# MotherBoard_ver1.net
KiCad netlist of a schematic drawn in EAGLE
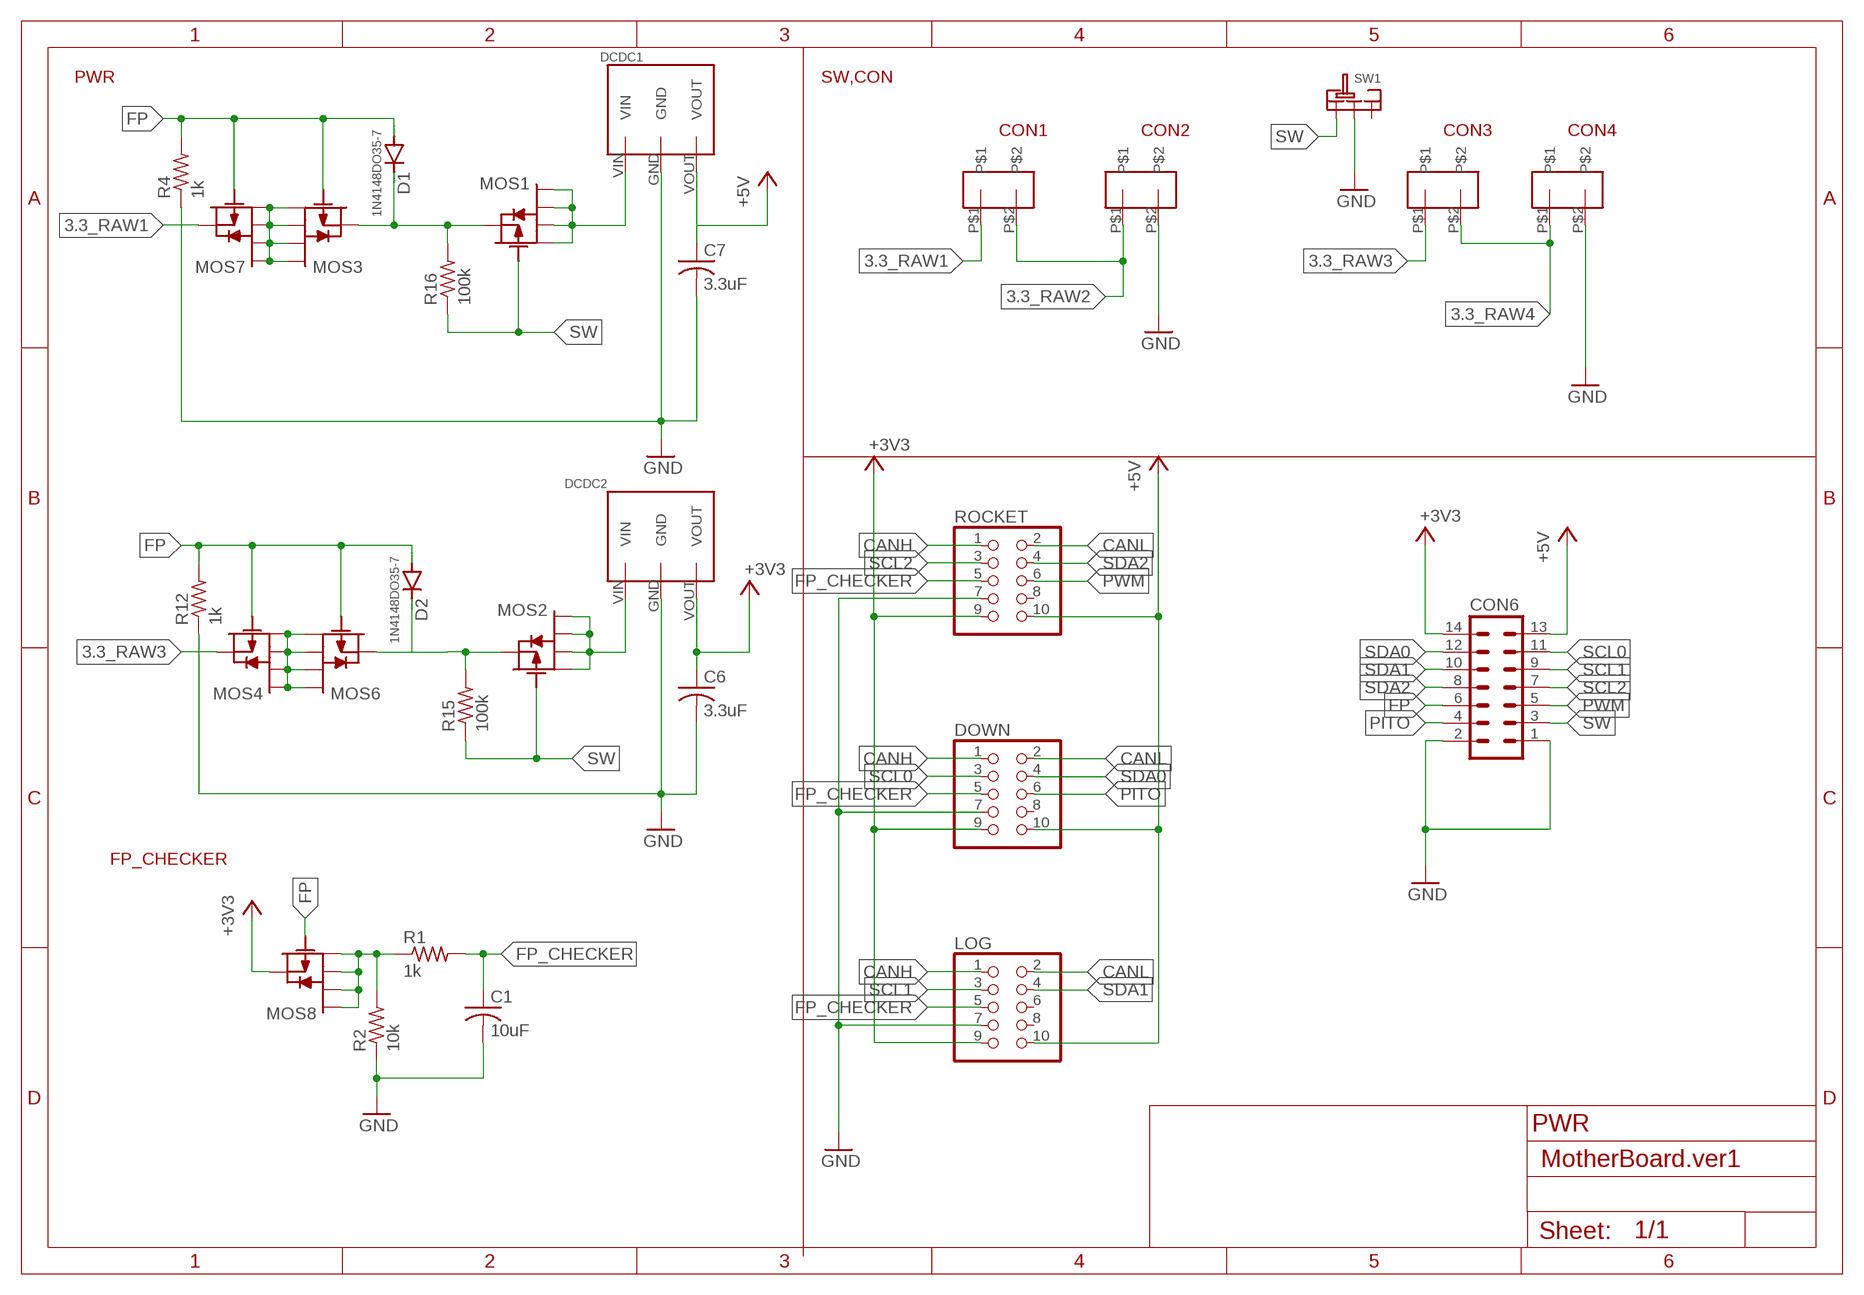
[diagram p0: schematic, sheet 1]

(export (version "E")
  (design (tool "Eeschema 10.0.6"))
  (components
    (comp (ref "C1")
      (value "10uF")
      (footprint "eagle-import:C0603")
      (libsource (lib "eagle-import") (part "C-USC0603"))
    )
    (comp (ref "C6")
      (value "3.3uF")
      (footprint "eagle-import:C0603")
      (libsource (lib "eagle-import") (part "C-USC0603"))
    )
    (comp (ref "C7")
      (value "3.3uF")
      (footprint "eagle-import:C0603")
      (libsource (lib "eagle-import") (part "C-USC0603"))
    )
    (comp (ref "CON1")
      (value "1.25CON2PIN")
      (footprint "eagle-import:1.25CON2PIN")
      (libsource (lib "eagle-import") (part "1.25CON2PIN"))
    )
    (comp (ref "CON2")
      (value "1.25CON2PIN")
      (footprint "eagle-import:1.25CON2PIN")
      (libsource (lib "eagle-import") (part "1.25CON2PIN"))
    )
    (comp (ref "CON3")
      (value "1.25CON2PIN")
      (footprint "eagle-import:1.25CON2PIN")
      (libsource (lib "eagle-import") (part "1.25CON2PIN"))
    )
    (comp (ref "CON4")
      (value "1.25CON2PIN")
      (footprint "eagle-import:1.25CON2PIN")
      (libsource (lib "eagle-import") (part "1.25CON2PIN"))
    )
    (comp (ref "CON6")
      (value "ML14L")
      (footprint "eagle-import:ML14L")
      (libsource (lib "eagle-import") (part "ML14L"))
    )
    (comp (ref "D1")
      (value "1N4148DO35-7")
      (footprint "eagle-import:DO35-7")
      (libsource (lib "eagle-import") (part "1N4148DO35-7"))
    )
    (comp (ref "D2")
      (value "1N4148DO35-7")
      (footprint "eagle-import:DO35-7")
      (libsource (lib "eagle-import") (part "1N4148DO35-7"))
    )
    (comp (ref "DCDC1")
      (value "5V1A_M78AR05-1")
      (footprint "eagle-import:5V1A_M78AR05-1")
      (libsource (lib "eagle-import") (part "5V1A_M78AR05-1"))
    )
    (comp (ref "DCDC2")
      (value "3.3V1A_M78AR033-1")
      (footprint "eagle-import:3.3V1A_M78AR033-1")
      (libsource (lib "eagle-import") (part "3.3V1A_M78AR033-1"))
    )
    (comp (ref "DOWN")
      (value "PINHD-2X5")
      (footprint "eagle-import:2X05")
      (libsource (lib "eagle-import") (part "PINHD-2X5"))
    )
    (comp (ref "LOG")
      (value "PINHD-2X5")
      (footprint "eagle-import:2X05")
      (libsource (lib "eagle-import") (part "PINHD-2X5"))
    )
    (comp (ref "MOS1")
      (value "PCH_SSM6J808R")
      (footprint "eagle-import:SSM6J808R")
      (libsource (lib "eagle-import") (part "PCH_SSM6J808R"))
    )
    (comp (ref "MOS2")
      (value "PCH_SSM6J808R")
      (footprint "eagle-import:SSM6J808R")
      (libsource (lib "eagle-import") (part "PCH_SSM6J808R"))
    )
    (comp (ref "MOS3")
      (value "PCH_SSM6J808R")
      (footprint "eagle-import:SSM6J808R")
      (libsource (lib "eagle-import") (part "PCH_SSM6J808R"))
    )
    (comp (ref "MOS4")
      (value "PCH_SSM6J808R")
      (footprint "eagle-import:SSM6J808R")
      (libsource (lib "eagle-import") (part "PCH_SSM6J808R"))
    )
    (comp (ref "MOS6")
      (value "PCH_SSM6J808R")
      (footprint "eagle-import:SSM6J808R")
      (libsource (lib "eagle-import") (part "PCH_SSM6J808R"))
    )
    (comp (ref "MOS7")
      (value "PCH_SSM6J808R")
      (footprint "eagle-import:SSM6J808R")
      (libsource (lib "eagle-import") (part "PCH_SSM6J808R"))
    )
    (comp (ref "MOS8")
      (value "PCH_SSM6J808R")
      (footprint "eagle-import:SSM6J808R")
      (libsource (lib "eagle-import") (part "PCH_SSM6J808R"))
    )
    (comp (ref "R1")
      (value "1k")
      (footprint "eagle-import:R0603")
      (libsource (lib "eagle-import") (part "R-US_R0603"))
    )
    (comp (ref "R2")
      (value "10k")
      (footprint "eagle-import:R0603")
      (libsource (lib "eagle-import") (part "R-US_R0603"))
    )
    (comp (ref "R4")
      (value "1k")
      (footprint "eagle-import:R0603")
      (libsource (lib "eagle-import") (part "R-US_R0603"))
    )
    (comp (ref "R12")
      (value "1k")
      (footprint "eagle-import:R0603")
      (libsource (lib "eagle-import") (part "R-US_R0603"))
    )
    (comp (ref "R15")
      (value "100k")
      (footprint "eagle-import:R0603")
      (libsource (lib "eagle-import") (part "R-US_R0603"))
    )
    (comp (ref "R16")
      (value "100k")
      (footprint "eagle-import:R0603")
      (libsource (lib "eagle-import") (part "R-US_R0603"))
    )
    (comp (ref "ROCKET")
      (value "PINHD-2X5")
      (footprint "eagle-import:2X05")
      (libsource (lib "eagle-import") (part "PINHD-2X5"))
    )
    (comp (ref "SW1")
      (value "SRIDE_SWITCH")
      (footprint "eagle-import:SRIDE_SWITCH")
      (libsource (lib "eagle-import") (part "SRIDE_SWITCH"))
    )
  )
  (nets
    (net (code "1") (name "+3V3") (class "Default")
      (node (ref "C6") (pin "1") (pinfunction "1_1") (pintype "passive"))
      (node (ref "CON6") (pin "14") (pinfunction "14_14") (pintype "passive"))
      (node (ref "DCDC2") (pin "VOUT") (pinfunction "VOUT_VOUT") (pintype "bidirectional"))
      (node (ref "DOWN") (pin "9") (pinfunction "9_9") (pintype "passive"))
      (node (ref "LOG") (pin "9") (pinfunction "9_9") (pintype "passive"))
      (node (ref "MOS8") (pin "4") (pinfunction "4_4") (pintype "bidirectional"))
      (node (ref "ROCKET") (pin "9") (pinfunction "9_9") (pintype "passive"))
    )
    (net (code "2") (name "+5V") (class "Default")
      (node (ref "C7") (pin "1") (pinfunction "1_1") (pintype "passive"))
      (node (ref "CON6") (pin "13") (pinfunction "13_13") (pintype "passive"))
      (node (ref "DCDC1") (pin "VOUT") (pinfunction "VOUT_VOUT") (pintype "bidirectional"))
      (node (ref "DOWN") (pin "10") (pinfunction "10_10") (pintype "passive"))
      (node (ref "LOG") (pin "10") (pinfunction "10_10") (pintype "passive"))
      (node (ref "ROCKET") (pin "10") (pinfunction "10_10") (pintype "passive"))
    )
    (net (code "3") (name "3.3_RAW1") (class "Default")
      (node (ref "CON1") (pin "P$1") (pinfunction "P$1_P$1") (pintype "bidirectional"))
      (node (ref "MOS7") (pin "4") (pinfunction "4_4") (pintype "bidirectional"))
    )
    (net (code "4") (name "3.3_RAW2") (class "Default")
      (node (ref "CON1") (pin "P$2") (pinfunction "P$2_P$2") (pintype "bidirectional"))
      (node (ref "CON2") (pin "P$1") (pinfunction "P$1_P$1") (pintype "bidirectional"))
    )
    (net (code "5") (name "3.3_RAW3") (class "Default")
      (node (ref "CON3") (pin "P$1") (pinfunction "P$1_P$1") (pintype "bidirectional"))
      (node (ref "MOS4") (pin "4") (pinfunction "4_4") (pintype "bidirectional"))
    )
    (net (code "6") (name "3.3_RAW4") (class "Default")
      (node (ref "CON3") (pin "P$2") (pinfunction "P$2_P$2") (pintype "bidirectional"))
      (node (ref "CON4") (pin "P$1") (pinfunction "P$1_P$1") (pintype "bidirectional"))
    )
    (net (code "7") (name "CANH") (class "Default")
      (node (ref "DOWN") (pin "1") (pinfunction "1_1") (pintype "passive"))
      (node (ref "LOG") (pin "1") (pinfunction "1_1") (pintype "passive"))
      (node (ref "ROCKET") (pin "1") (pinfunction "1_1") (pintype "passive"))
    )
    (net (code "8") (name "CANL") (class "Default")
      (node (ref "DOWN") (pin "2") (pinfunction "2_2") (pintype "passive"))
      (node (ref "LOG") (pin "2") (pinfunction "2_2") (pintype "passive"))
      (node (ref "ROCKET") (pin "2") (pinfunction "2_2") (pintype "passive"))
    )
    (net (code "9") (name "FP") (class "Default")
      (node (ref "CON6") (pin "6") (pinfunction "6_6") (pintype "passive"))
      (node (ref "D1") (pin "A") (pinfunction "A_A") (pintype "passive"))
      (node (ref "D2") (pin "A") (pinfunction "A_A") (pintype "passive"))
      (node (ref "MOS3") (pin "3") (pinfunction "3_3") (pintype "bidirectional"))
      (node (ref "MOS4") (pin "3") (pinfunction "3_3") (pintype "bidirectional"))
      (node (ref "MOS6") (pin "3") (pinfunction "3_3") (pintype "bidirectional"))
      (node (ref "MOS7") (pin "3") (pinfunction "3_3") (pintype "bidirectional"))
      (node (ref "MOS8") (pin "3") (pinfunction "3_3") (pintype "bidirectional"))
      (node (ref "R12") (pin "2") (pinfunction "2_2") (pintype "passive"))
      (node (ref "R4") (pin "2") (pinfunction "2_2") (pintype "passive"))
    )
    (net (code "10") (name "FP_CHECKER") (class "Default")
      (node (ref "C1") (pin "1") (pinfunction "1_1") (pintype "passive"))
      (node (ref "DOWN") (pin "5") (pinfunction "5_5") (pintype "passive"))
      (node (ref "LOG") (pin "5") (pinfunction "5_5") (pintype "passive"))
      (node (ref "R1") (pin "2") (pinfunction "2_2") (pintype "passive"))
      (node (ref "ROCKET") (pin "5") (pinfunction "5_5") (pintype "passive"))
    )
    (net (code "11") (name "GND") (class "Default")
      (node (ref "C1") (pin "2") (pinfunction "2_2") (pintype "passive"))
      (node (ref "C6") (pin "2") (pinfunction "2_2") (pintype "passive"))
      (node (ref "C7") (pin "2") (pinfunction "2_2") (pintype "passive"))
      (node (ref "CON2") (pin "P$2") (pinfunction "P$2_P$2") (pintype "bidirectional"))
      (node (ref "CON4") (pin "P$2") (pinfunction "P$2_P$2") (pintype "bidirectional"))
      (node (ref "CON6") (pin "1") (pinfunction "1_1") (pintype "passive"))
      (node (ref "CON6") (pin "2") (pinfunction "2_2") (pintype "passive"))
      (node (ref "DCDC1") (pin "GND") (pinfunction "GND_GND") (pintype "bidirectional"))
      (node (ref "DCDC2") (pin "GND") (pinfunction "GND_GND") (pintype "bidirectional"))
      (node (ref "DOWN") (pin "7") (pinfunction "7_7") (pintype "passive"))
      (node (ref "LOG") (pin "7") (pinfunction "7_7") (pintype "passive"))
      (node (ref "R12") (pin "1") (pinfunction "1_1") (pintype "passive"))
      (node (ref "R2") (pin "1") (pinfunction "1_1") (pintype "passive"))
      (node (ref "R4") (pin "1") (pinfunction "1_1") (pintype "passive"))
      (node (ref "ROCKET") (pin "7") (pinfunction "7_7") (pintype "passive"))
      (node (ref "SW1") (pin "LR") (pinfunction "LR_LR") (pintype "bidirectional"))
    )
    (net (code "12") (name "Net-(D1-PadC)") (class "Default")
      (node (ref "D1") (pin "C") (pinfunction "C_C") (pintype "passive"))
      (node (ref "MOS1") (pin "4") (pinfunction "4_4") (pintype "bidirectional"))
      (node (ref "MOS3") (pin "4") (pinfunction "4_4") (pintype "bidirectional"))
      (node (ref "R16") (pin "2") (pinfunction "2_2") (pintype "passive"))
    )
    (net (code "13") (name "Net-(D2-PadC)") (class "Default")
      (node (ref "D2") (pin "C") (pinfunction "C_C") (pintype "passive"))
      (node (ref "MOS2") (pin "4") (pinfunction "4_4") (pintype "bidirectional"))
      (node (ref "MOS6") (pin "4") (pinfunction "4_4") (pintype "bidirectional"))
      (node (ref "R15") (pin "2") (pinfunction "2_2") (pintype "passive"))
    )
    (net (code "14") (name "Net-(DCDC1-PadVIN)") (class "Default")
      (node (ref "DCDC1") (pin "VIN") (pinfunction "VIN_VIN") (pintype "bidirectional"))
      (node (ref "MOS1") (pin "1") (pinfunction "1_1") (pintype "bidirectional"))
      (node (ref "MOS1") (pin "2") (pinfunction "2_2") (pintype "bidirectional"))
      (node (ref "MOS1") (pin "5") (pinfunction "5_5") (pintype "bidirectional"))
      (node (ref "MOS1") (pin "6") (pinfunction "6_6") (pintype "bidirectional"))
    )
    (net (code "15") (name "Net-(DCDC2-PadVIN)") (class "Default")
      (node (ref "DCDC2") (pin "VIN") (pinfunction "VIN_VIN") (pintype "bidirectional"))
      (node (ref "MOS2") (pin "1") (pinfunction "1_1") (pintype "bidirectional"))
      (node (ref "MOS2") (pin "2") (pinfunction "2_2") (pintype "bidirectional"))
      (node (ref "MOS2") (pin "5") (pinfunction "5_5") (pintype "bidirectional"))
      (node (ref "MOS2") (pin "6") (pinfunction "6_6") (pintype "bidirectional"))
    )
    (net (code "16") (name "Net-(MOS3-Pad1)") (class "Default")
      (node (ref "MOS3") (pin "1") (pinfunction "1_1") (pintype "bidirectional"))
      (node (ref "MOS3") (pin "2") (pinfunction "2_2") (pintype "bidirectional"))
      (node (ref "MOS3") (pin "5") (pinfunction "5_5") (pintype "bidirectional"))
      (node (ref "MOS3") (pin "6") (pinfunction "6_6") (pintype "bidirectional"))
      (node (ref "MOS7") (pin "1") (pinfunction "1_1") (pintype "bidirectional"))
      (node (ref "MOS7") (pin "2") (pinfunction "2_2") (pintype "bidirectional"))
      (node (ref "MOS7") (pin "5") (pinfunction "5_5") (pintype "bidirectional"))
      (node (ref "MOS7") (pin "6") (pinfunction "6_6") (pintype "bidirectional"))
    )
    (net (code "17") (name "Net-(MOS4-Pad1)") (class "Default")
      (node (ref "MOS4") (pin "1") (pinfunction "1_1") (pintype "bidirectional"))
      (node (ref "MOS4") (pin "2") (pinfunction "2_2") (pintype "bidirectional"))
      (node (ref "MOS4") (pin "5") (pinfunction "5_5") (pintype "bidirectional"))
      (node (ref "MOS4") (pin "6") (pinfunction "6_6") (pintype "bidirectional"))
      (node (ref "MOS6") (pin "1") (pinfunction "1_1") (pintype "bidirectional"))
      (node (ref "MOS6") (pin "2") (pinfunction "2_2") (pintype "bidirectional"))
      (node (ref "MOS6") (pin "5") (pinfunction "5_5") (pintype "bidirectional"))
      (node (ref "MOS6") (pin "6") (pinfunction "6_6") (pintype "bidirectional"))
    )
    (net (code "18") (name "Net-(MOS8-Pad1)") (class "Default")
      (node (ref "MOS8") (pin "1") (pinfunction "1_1") (pintype "bidirectional"))
      (node (ref "MOS8") (pin "2") (pinfunction "2_2") (pintype "bidirectional"))
      (node (ref "MOS8") (pin "5") (pinfunction "5_5") (pintype "bidirectional"))
      (node (ref "MOS8") (pin "6") (pinfunction "6_6") (pintype "bidirectional"))
      (node (ref "R1") (pin "1") (pinfunction "1_1") (pintype "passive"))
      (node (ref "R2") (pin "2") (pinfunction "2_2") (pintype "passive"))
    )
    (net (code "19") (name "PITO") (class "Default")
      (node (ref "CON6") (pin "4") (pinfunction "4_4") (pintype "passive"))
      (node (ref "DOWN") (pin "6") (pinfunction "6_6") (pintype "passive"))
    )
    (net (code "20") (name "PWM") (class "Default")
      (node (ref "CON6") (pin "5") (pinfunction "5_5") (pintype "passive"))
      (node (ref "ROCKET") (pin "6") (pinfunction "6_6") (pintype "passive"))
    )
    (net (code "21") (name "SCL0") (class "Default")
      (node (ref "CON6") (pin "11") (pinfunction "11_11") (pintype "passive"))
      (node (ref "DOWN") (pin "3") (pinfunction "3_3") (pintype "passive"))
    )
    (net (code "22") (name "SCL1") (class "Default")
      (node (ref "CON6") (pin "9") (pinfunction "9_9") (pintype "passive"))
      (node (ref "LOG") (pin "3") (pinfunction "3_3") (pintype "passive"))
    )
    (net (code "23") (name "SCL2") (class "Default")
      (node (ref "CON6") (pin "7") (pinfunction "7_7") (pintype "passive"))
      (node (ref "ROCKET") (pin "3") (pinfunction "3_3") (pintype "passive"))
    )
    (net (code "24") (name "SDA0") (class "Default")
      (node (ref "CON6") (pin "12") (pinfunction "12_12") (pintype "passive"))
      (node (ref "DOWN") (pin "4") (pinfunction "4_4") (pintype "passive"))
    )
    (net (code "25") (name "SDA1") (class "Default")
      (node (ref "CON6") (pin "10") (pinfunction "10_10") (pintype "passive"))
      (node (ref "LOG") (pin "4") (pinfunction "4_4") (pintype "passive"))
    )
    (net (code "26") (name "SDA2") (class "Default")
      (node (ref "CON6") (pin "8") (pinfunction "8_8") (pintype "passive"))
      (node (ref "ROCKET") (pin "4") (pinfunction "4_4") (pintype "passive"))
    )
    (net (code "27") (name "SW") (class "Default")
      (node (ref "CON6") (pin "3") (pinfunction "3_3") (pintype "passive"))
      (node (ref "MOS1") (pin "3") (pinfunction "3_3") (pintype "bidirectional"))
      (node (ref "MOS2") (pin "3") (pinfunction "3_3") (pintype "bidirectional"))
      (node (ref "R15") (pin "1") (pinfunction "1_1") (pintype "passive"))
      (node (ref "R16") (pin "1") (pinfunction "1_1") (pintype "passive"))
      (node (ref "SW1") (pin "L") (pinfunction "L_L") (pintype "bidirectional"))
    )
    (net (code "28") (name "unconnected-(DOWN-Pad8)") (class "Default")
      (node (ref "DOWN") (pin "8") (pinfunction "8_8") (pintype "passive"))
    )
    (net (code "29") (name "unconnected-(LOG-Pad6)") (class "Default")
      (node (ref "LOG") (pin "6") (pinfunction "6_6") (pintype "passive"))
    )
    (net (code "30") (name "unconnected-(LOG-Pad8)") (class "Default")
      (node (ref "LOG") (pin "8") (pinfunction "8_8") (pintype "passive"))
    )
    (net (code "31") (name "unconnected-(ROCKET-Pad8)") (class "Default")
      (node (ref "ROCKET") (pin "8") (pinfunction "8_8") (pintype "passive"))
    )
    (net (code "32") (name "unconnected-(SW1-PadR)") (class "Default")
      (node (ref "SW1") (pin "R") (pinfunction "R_R") (pintype "bidirectional"))
    )
  )
)
